# QCLogic_Rev_A_Sht8_MCU_Power.net
KiCad netlist of a schematic drawn in Altium Designer
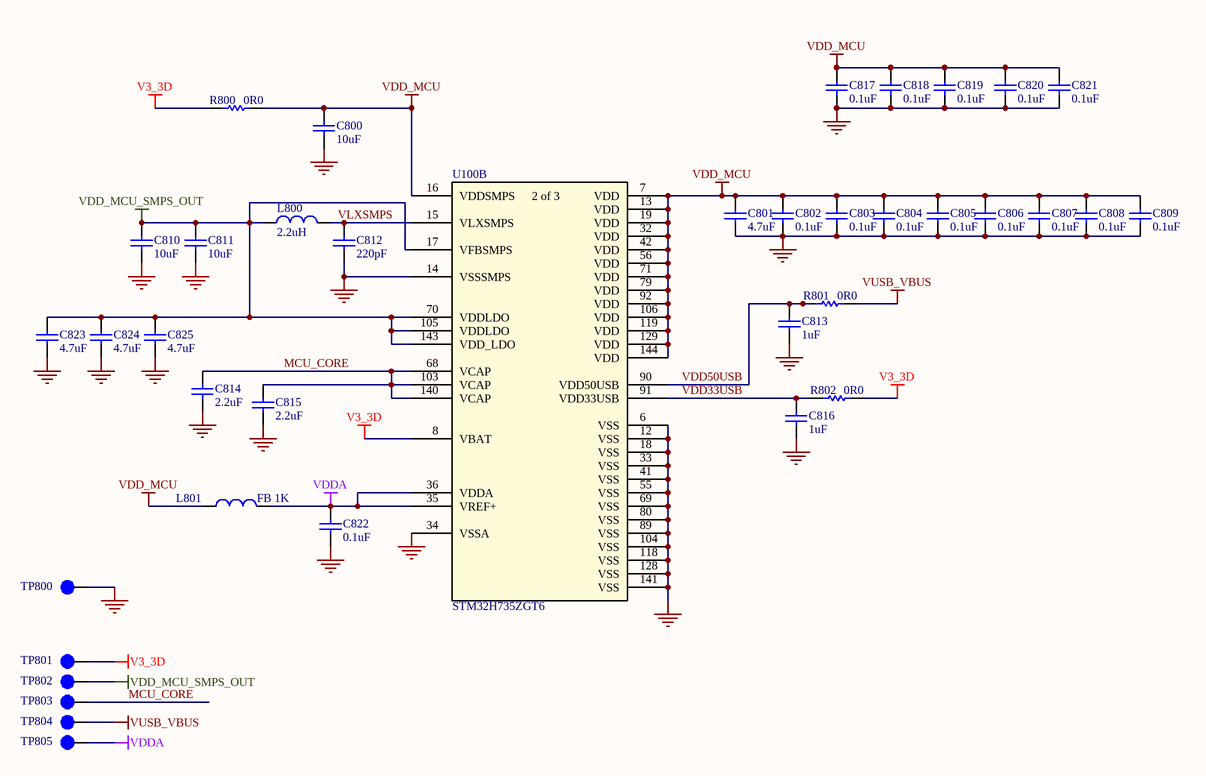
[diagram p0: QCLogic Rev A Sht8 MCU Power.SchDoc]

(export (version "E")
  (design (tool "Eeschema 10.0.6"))
  (components
    (comp (ref "C800")
      (value "10uF")
      (footprint "SMD CAP 0805")
      (description "CAP CER 10UF 25V X5R 0805")
      (fields (field (name "2. MANUFACTURER PART NUMBER") "TMK212BBJ106KG-T"))
      (libsource (lib "SBCLib") (part "CAP MLCC SMD"))
    )
    (comp (ref "C801")
      (value "4.7uF")
      (footprint "SMD CAP 0603")
      (description "CAP CER 4.7UF 16V X7S 0603")
      (fields (field (name "2. MANUFACTURER PART NUMBER") "GRM188C71C475KE21D"))
      (libsource (lib "SBCLib") (part "CAP MLCC SMD"))
    )
    (comp (ref "C802")
      (value "0.1uF")
      (footprint "SMD CAP 0402")
      (description "CAP CER 0.1UF 25V X7R 0402")
      (fields (field (name "2. MANUFACTURER PART NUMBER") "CC0402KRX7R8BB104"))
      (libsource (lib "SBCLib") (part "CAP MLCC SMD"))
    )
    (comp (ref "C803")
      (value "0.1uF")
      (footprint "SMD CAP 0402")
      (description "CAP CER 0.1UF 25V X7R 0402")
      (fields (field (name "2. MANUFACTURER PART NUMBER") "CC0402KRX7R8BB104"))
      (libsource (lib "SBCLib") (part "CAP MLCC SMD"))
    )
    (comp (ref "C804")
      (value "0.1uF")
      (footprint "SMD CAP 0402")
      (description "CAP CER 0.1UF 25V X7R 0402")
      (fields (field (name "2. MANUFACTURER PART NUMBER") "CC0402KRX7R8BB104"))
      (libsource (lib "SBCLib") (part "CAP MLCC SMD"))
    )
    (comp (ref "C805")
      (value "0.1uF")
      (footprint "SMD CAP 0402")
      (description "CAP CER 0.1UF 25V X7R 0402")
      (fields (field (name "2. MANUFACTURER PART NUMBER") "CC0402KRX7R8BB104"))
      (libsource (lib "SBCLib") (part "CAP MLCC SMD"))
    )
    (comp (ref "C806")
      (value "0.1uF")
      (footprint "SMD CAP 0402")
      (description "CAP CER 0.1UF 25V X7R 0402")
      (fields (field (name "2. MANUFACTURER PART NUMBER") "CC0402KRX7R8BB104"))
      (libsource (lib "SBCLib") (part "CAP MLCC SMD"))
    )
    (comp (ref "C807")
      (value "0.1uF")
      (footprint "SMD CAP 0402")
      (description "CAP CER 0.1UF 25V X7R 0402")
      (fields (field (name "2. MANUFACTURER PART NUMBER") "CC0402KRX7R8BB104"))
      (libsource (lib "SBCLib") (part "CAP MLCC SMD"))
    )
    (comp (ref "C808")
      (value "0.1uF")
      (footprint "SMD CAP 0402")
      (description "CAP CER 0.1UF 25V X7R 0402")
      (fields (field (name "2. MANUFACTURER PART NUMBER") "CC0402KRX7R8BB104"))
      (libsource (lib "SBCLib") (part "CAP MLCC SMD"))
    )
    (comp (ref "C809")
      (value "0.1uF")
      (footprint "SMD CAP 0402")
      (description "CAP CER 0.1UF 25V X7R 0402")
      (fields (field (name "2. MANUFACTURER PART NUMBER") "CC0402KRX7R8BB104"))
      (libsource (lib "SBCLib") (part "CAP MLCC SMD"))
    )
    (comp (ref "C810")
      (value "10uF")
      (footprint "SMD CAP 0805")
      (description "CAP CER 10UF 25V X5R 0805")
      (fields (field (name "2. MANUFACTURER PART NUMBER") "TMK212BBJ106KG-T"))
      (libsource (lib "SBCLib") (part "CAP MLCC SMD"))
    )
    (comp (ref "C811")
      (value "10uF")
      (footprint "SMD CAP 0805")
      (description "CAP CER 10UF 25V X5R 0805")
      (fields (field (name "2. MANUFACTURER PART NUMBER") "TMK212BBJ106KG-T"))
      (libsource (lib "SBCLib") (part "CAP MLCC SMD"))
    )
    (comp (ref "C812")
      (value "220pF")
      (footprint "SMD CAP 0402")
      (description "CAP CER 220PF 50V X7R 0402")
      (fields (field (name "2. MANUFACTURER PART NUMBER") "CC0402KRX7R9BB221"))
      (libsource (lib "SBCLib") (part "CAP MLCC SMD"))
    )
    (comp (ref "C813")
      (value "1uF")
      (footprint "SMD CAP 0402")
      (description "CAP CER 1UF 25V X5R 0402")
      (fields (field (name "2. MANUFACTURER PART NUMBER") "GRT155R61E105KE01D"))
      (libsource (lib "SBCLib") (part "CAP MLCC SMD"))
    )
    (comp (ref "C814")
      (value "2.2uF")
      (footprint "SMD CAP 0402")
      (description "CAP CER 2.2UF 16V X6S 0402")
      (fields (field (name "2. MANUFACTURER PART NUMBER") "GRM155C81C225ME15D"))
      (libsource (lib "SBCLib") (part "CAP MLCC SMD"))
    )
    (comp (ref "C815")
      (value "2.2uF")
      (footprint "SMD CAP 0402")
      (description "CAP CER 2.2UF 16V X6S 0402")
      (fields (field (name "2. MANUFACTURER PART NUMBER") "GRM155C81C225ME15D"))
      (libsource (lib "SBCLib") (part "CAP MLCC SMD"))
    )
    (comp (ref "C816")
      (value "1uF")
      (footprint "SMD CAP 0402")
      (description "CAP CER 1UF 25V X5R 0402")
      (fields (field (name "2. MANUFACTURER PART NUMBER") "GRT155R61E105KE01D"))
      (libsource (lib "SBCLib") (part "CAP MLCC SMD"))
    )
    (comp (ref "C817")
      (value "0.1uF")
      (footprint "SMD CAP 0402")
      (description "CAP CER 0.1UF 25V X7R 0402")
      (fields (field (name "2. MANUFACTURER PART NUMBER") "CC0402KRX7R8BB104"))
      (libsource (lib "SBCLib") (part "CAP MLCC SMD"))
    )
    (comp (ref "C818")
      (value "0.1uF")
      (footprint "SMD CAP 0402")
      (description "CAP CER 0.1UF 25V X7R 0402")
      (fields (field (name "2. MANUFACTURER PART NUMBER") "CC0402KRX7R8BB104"))
      (libsource (lib "SBCLib") (part "CAP MLCC SMD"))
    )
    (comp (ref "C819")
      (value "0.1uF")
      (footprint "SMD CAP 0402")
      (description "CAP CER 0.1UF 25V X7R 0402")
      (fields (field (name "2. MANUFACTURER PART NUMBER") "CC0402KRX7R8BB104"))
      (libsource (lib "SBCLib") (part "CAP MLCC SMD"))
    )
    (comp (ref "C820")
      (value "0.1uF")
      (footprint "SMD CAP 0402")
      (description "CAP CER 0.1UF 25V X7R 0402")
      (fields (field (name "2. MANUFACTURER PART NUMBER") "CC0402KRX7R8BB104"))
      (libsource (lib "SBCLib") (part "CAP MLCC SMD"))
    )
    (comp (ref "C821")
      (value "0.1uF")
      (footprint "SMD CAP 0402")
      (description "CAP CER 0.1UF 25V X7R 0402")
      (fields (field (name "2. MANUFACTURER PART NUMBER") "CC0402KRX7R8BB104"))
      (libsource (lib "SBCLib") (part "CAP MLCC SMD"))
    )
    (comp (ref "C822")
      (value "0.1uF")
      (footprint "SMD CAP 0402")
      (description "CAP CER 0.1UF 25V X7R 0402")
      (fields (field (name "2. MANUFACTURER PART NUMBER") "CC0402KRX7R8BB104"))
      (libsource (lib "SBCLib") (part "CAP MLCC SMD"))
    )
    (comp (ref "C823")
      (value "4.7uF")
      (footprint "SMD CAP 0603")
      (description "CAP CER 4.7UF 16V X7S 0603")
      (fields (field (name "2. MANUFACTURER PART NUMBER") "GRM188C71C475KE21D"))
      (libsource (lib "SBCLib") (part "CAP MLCC SMD"))
    )
    (comp (ref "C824")
      (value "4.7uF")
      (footprint "SMD CAP 0603")
      (description "CAP CER 4.7UF 16V X7S 0603")
      (fields (field (name "2. MANUFACTURER PART NUMBER") "GRM188C71C475KE21D"))
      (libsource (lib "SBCLib") (part "CAP MLCC SMD"))
    )
    (comp (ref "C825")
      (value "4.7uF")
      (footprint "SMD CAP 0603")
      (description "CAP CER 4.7UF 16V X7S 0603")
      (fields (field (name "2. MANUFACTURER PART NUMBER") "GRM188C71C475KE21D"))
      (libsource (lib "SBCLib") (part "CAP MLCC SMD"))
    )
    (comp (ref "L800")
      (value "2.2uH")
      (footprint "IND SMD 0806")
      (description "IND FIXED 2.2UH 1.2A 138 MOHM")
      (fields (field (name "2. MANUFACTURER PART NUMBER") "LQM2MPN2R2NG0L"))
      (libsource (lib "SBCLib") (part "INDUCTOR"))
    )
    (comp (ref "L801")
      (value "FB 1K")
      (footprint "SMD RES 0402")
      (description "FERRITE BEAD 1 KOHM 0402 1LN")
      (fields (field (name "2. MANUFACTURER PART NUMBER") "BLM15HD102SN1D"))
      (libsource (lib "SBCLib") (part "INDUCTOR"))
    )
    (comp (ref "R800")
      (value "0R0")
      (footprint "SMD RES 0402")
      (description "RES SMD 0 OHM JUMPER 1/16W 0402")
      (fields (field (name "2. MANUFACTURER PART NUMBER") "RC0402FR-070RL"))
      (libsource (lib "SBCLib") (part "RES SMD"))
    )
    (comp (ref "R801")
      (value "0R0")
      (footprint "SMD RES 0402")
      (description "RES SMD 0 OHM JUMPER 1/16W 0402")
      (fields (field (name "2. MANUFACTURER PART NUMBER") "RC0402FR-070RL"))
      (libsource (lib "SBCLib") (part "RES SMD"))
    )
    (comp (ref "R802")
      (value "0R0")
      (footprint "SMD RES 0402")
      (description "RES SMD 0 OHM JUMPER 1/16W 0402")
      (fields (field (name "2. MANUFACTURER PART NUMBER") "RC0402FR-070RL"))
      (libsource (lib "SBCLib") (part "RES SMD"))
    )
    (comp (ref "TP800")
      (value "TESTPOINT SMD")
      (footprint "TESTPOINT 1mm DIA")
      (description "TESTPOINT SMD PAD")
      (libsource (lib "SBCLib") (part "TESTPOINT PAD"))
    )
    (comp (ref "TP801")
      (value "TESTPOINT SMD")
      (footprint "TESTPOINT 0.5mm DIA")
      (description "TESTPOINT SMD PAD")
      (libsource (lib "SBCLib") (part "TESTPOINT PAD"))
    )
    (comp (ref "TP802")
      (value "TESTPOINT SMD")
      (footprint "TESTPOINT 0.5mm DIA")
      (description "TESTPOINT SMD PAD")
      (libsource (lib "SBCLib") (part "TESTPOINT PAD"))
    )
    (comp (ref "TP803")
      (value "TESTPOINT SMD")
      (footprint "TESTPOINT 0.5mm DIA")
      (description "TESTPOINT SMD PAD")
      (libsource (lib "SBCLib") (part "TESTPOINT PAD"))
    )
    (comp (ref "TP804")
      (value "TESTPOINT SMD")
      (footprint "TESTPOINT 0.5mm DIA")
      (description "TESTPOINT SMD PAD")
      (libsource (lib "SBCLib") (part "TESTPOINT PAD"))
    )
    (comp (ref "TP805")
      (value "TESTPOINT SMD")
      (footprint "TESTPOINT 0.5mm DIA")
      (description "TESTPOINT SMD PAD")
      (libsource (lib "SBCLib") (part "TESTPOINT PAD"))
    )
    (comp (ref "U100")
      (value "STM32H735ZGT6")
      (footprint "LQFP-144 20x20")
      (description "ARM® Cortex®-M7 STM32H7 Microcontroller IC 32-Bit 550MHz 1MB (1M x 8) FLASH 144 LQFP 20x20")
      (libsource (lib "SBCLib") (part "IC MCU STM32H735ZG Arm M7"))
    )
  )
  (nets
    (net (code "1") (name "/MCU_CORE") (class "Default")
      (node (ref "C814") (pin "2") (pinfunction "2_2") (pintype "passive"))
      (node (ref "C815") (pin "2") (pinfunction "2_2") (pintype "passive"))
      (node (ref "TP803") (pin "1") (pinfunction "1_1") (pintype "passive"))
      (node (ref "U100") (pin "103") (pinfunction "VCAP_103") (pintype "passive"))
      (node (ref "U100") (pin "140") (pinfunction "VCAP_140") (pintype "passive"))
      (node (ref "U100") (pin "68") (pinfunction "VCAP_68") (pintype "passive"))
    )
    (net (code "2") (name "/VDD33USB") (class "Default")
      (node (ref "C816") (pin "1") (pinfunction "1_1") (pintype "passive"))
      (node (ref "R802") (pin "1") (pinfunction "1_1") (pintype "passive"))
      (node (ref "U100") (pin "91") (pinfunction "VDD33USB_91") (pintype "passive"))
    )
    (net (code "3") (name "/VDD50USB") (class "Default")
      (node (ref "C813") (pin "1") (pinfunction "1_1") (pintype "passive"))
      (node (ref "R801") (pin "1") (pinfunction "1_1") (pintype "passive"))
      (node (ref "U100") (pin "90") (pinfunction "VDD50USB_90") (pintype "passive"))
    )
    (net (code "4") (name "/VLXSMPS") (class "Default")
      (node (ref "C812") (pin "2") (pinfunction "2_2") (pintype "passive"))
      (node (ref "L800") (pin "2") (pinfunction "2_2") (pintype "passive"))
      (node (ref "U100") (pin "15") (pinfunction "VLXSMPS_15") (pintype "passive"))
    )
    (net (code "5") (name "GND") (class "Default")
      (node (ref "C800") (pin "2") (pinfunction "2_2") (pintype "passive"))
      (node (ref "C801") (pin "2") (pinfunction "2_2") (pintype "passive"))
      (node (ref "C802") (pin "1") (pinfunction "1_1") (pintype "passive"))
      (node (ref "C803") (pin "1") (pinfunction "1_1") (pintype "passive"))
      (node (ref "C804") (pin "1") (pinfunction "1_1") (pintype "passive"))
      (node (ref "C805") (pin "1") (pinfunction "1_1") (pintype "passive"))
      (node (ref "C806") (pin "1") (pinfunction "1_1") (pintype "passive"))
      (node (ref "C807") (pin "1") (pinfunction "1_1") (pintype "passive"))
      (node (ref "C808") (pin "1") (pinfunction "1_1") (pintype "passive"))
      (node (ref "C809") (pin "1") (pinfunction "1_1") (pintype "passive"))
      (node (ref "C810") (pin "2") (pinfunction "2_2") (pintype "passive"))
      (node (ref "C811") (pin "2") (pinfunction "2_2") (pintype "passive"))
      (node (ref "C812") (pin "1") (pinfunction "1_1") (pintype "passive"))
      (node (ref "C813") (pin "2") (pinfunction "2_2") (pintype "passive"))
      (node (ref "C814") (pin "1") (pinfunction "1_1") (pintype "passive"))
      (node (ref "C815") (pin "1") (pinfunction "1_1") (pintype "passive"))
      (node (ref "C816") (pin "2") (pinfunction "2_2") (pintype "passive"))
      (node (ref "C817") (pin "1") (pinfunction "1_1") (pintype "passive"))
      (node (ref "C818") (pin "1") (pinfunction "1_1") (pintype "passive"))
      (node (ref "C819") (pin "1") (pinfunction "1_1") (pintype "passive"))
      (node (ref "C820") (pin "1") (pinfunction "1_1") (pintype "passive"))
      (node (ref "C821") (pin "1") (pinfunction "1_1") (pintype "passive"))
      (node (ref "C822") (pin "1") (pinfunction "1_1") (pintype "passive"))
      (node (ref "C823") (pin "2") (pinfunction "2_2") (pintype "passive"))
      (node (ref "C824") (pin "2") (pinfunction "2_2") (pintype "passive"))
      (node (ref "C825") (pin "2") (pinfunction "2_2") (pintype "passive"))
      (node (ref "TP800") (pin "1") (pinfunction "1_1") (pintype "passive"))
      (node (ref "U100") (pin "104") (pinfunction "VSS_104") (pintype "passive"))
      (node (ref "U100") (pin "118") (pinfunction "VSS_118") (pintype "passive"))
      (node (ref "U100") (pin "12") (pinfunction "VSS_12") (pintype "passive"))
      (node (ref "U100") (pin "128") (pinfunction "VSS_128") (pintype "passive"))
      (node (ref "U100") (pin "14") (pinfunction "VSSSMPS_14") (pintype "passive"))
      (node (ref "U100") (pin "141") (pinfunction "VSS_141") (pintype "passive"))
      (node (ref "U100") (pin "18") (pinfunction "VSS_18") (pintype "passive"))
      (node (ref "U100") (pin "33") (pinfunction "VSS_33") (pintype "passive"))
      (node (ref "U100") (pin "34") (pinfunction "VSSA_34") (pintype "passive"))
      (node (ref "U100") (pin "41") (pinfunction "VSS_41") (pintype "passive"))
      (node (ref "U100") (pin "55") (pinfunction "VSS_55") (pintype "passive"))
      (node (ref "U100") (pin "6") (pinfunction "VSS_6") (pintype "passive"))
      (node (ref "U100") (pin "69") (pinfunction "VSS_69") (pintype "passive"))
      (node (ref "U100") (pin "80") (pinfunction "VSS_80") (pintype "passive"))
      (node (ref "U100") (pin "89") (pinfunction "VSS_89") (pintype "passive"))
    )
    (net (code "6") (name "V3_3D") (class "Default")
      (node (ref "R800") (pin "1") (pinfunction "1_1") (pintype "passive"))
      (node (ref "R802") (pin "2") (pinfunction "2_2") (pintype "passive"))
      (node (ref "TP801") (pin "1") (pinfunction "1_1") (pintype "passive"))
      (node (ref "U100") (pin "8") (pinfunction "VBAT_8") (pintype "passive"))
    )
    (net (code "7") (name "VDDA") (class "Default")
      (node (ref "C822") (pin "2") (pinfunction "2_2") (pintype "passive"))
      (node (ref "L801") (pin "2") (pinfunction "2_2") (pintype "passive"))
      (node (ref "TP805") (pin "1") (pinfunction "1_1") (pintype "passive"))
      (node (ref "U100") (pin "35") (pinfunction "VREF+_35") (pintype "passive"))
      (node (ref "U100") (pin "36") (pinfunction "VDDA_36") (pintype "passive"))
    )
    (net (code "8") (name "VDD_MCU") (class "Default")
      (node (ref "C800") (pin "1") (pinfunction "1_1") (pintype "passive"))
      (node (ref "C801") (pin "1") (pinfunction "1_1") (pintype "passive"))
      (node (ref "C802") (pin "2") (pinfunction "2_2") (pintype "passive"))
      (node (ref "C803") (pin "2") (pinfunction "2_2") (pintype "passive"))
      (node (ref "C804") (pin "2") (pinfunction "2_2") (pintype "passive"))
      (node (ref "C805") (pin "2") (pinfunction "2_2") (pintype "passive"))
      (node (ref "C806") (pin "2") (pinfunction "2_2") (pintype "passive"))
      (node (ref "C807") (pin "2") (pinfunction "2_2") (pintype "passive"))
      (node (ref "C808") (pin "2") (pinfunction "2_2") (pintype "passive"))
      (node (ref "C809") (pin "2") (pinfunction "2_2") (pintype "passive"))
      (node (ref "C817") (pin "2") (pinfunction "2_2") (pintype "passive"))
      (node (ref "C818") (pin "2") (pinfunction "2_2") (pintype "passive"))
      (node (ref "C819") (pin "2") (pinfunction "2_2") (pintype "passive"))
      (node (ref "C820") (pin "2") (pinfunction "2_2") (pintype "passive"))
      (node (ref "C821") (pin "2") (pinfunction "2_2") (pintype "passive"))
      (node (ref "L801") (pin "1") (pinfunction "1_1") (pintype "passive"))
      (node (ref "R800") (pin "2") (pinfunction "2_2") (pintype "passive"))
      (node (ref "U100") (pin "106") (pinfunction "VDD_106") (pintype "passive"))
      (node (ref "U100") (pin "119") (pinfunction "VDD_119") (pintype "passive"))
      (node (ref "U100") (pin "129") (pinfunction "VDD_129") (pintype "passive"))
      (node (ref "U100") (pin "13") (pinfunction "VDD_13") (pintype "passive"))
      (node (ref "U100") (pin "144") (pinfunction "VDD_144") (pintype "passive"))
      (node (ref "U100") (pin "16") (pinfunction "VDDSMPS_16") (pintype "power_in"))
      (node (ref "U100") (pin "19") (pinfunction "VDD_19") (pintype "passive"))
      (node (ref "U100") (pin "32") (pinfunction "VDD_32") (pintype "passive"))
      (node (ref "U100") (pin "42") (pinfunction "VDD_42") (pintype "passive"))
      (node (ref "U100") (pin "56") (pinfunction "VDD_56") (pintype "passive"))
      (node (ref "U100") (pin "7") (pinfunction "VDD_7") (pintype "passive"))
      (node (ref "U100") (pin "71") (pinfunction "VDD_71") (pintype "passive"))
      (node (ref "U100") (pin "79") (pinfunction "VDD_79") (pintype "passive"))
      (node (ref "U100") (pin "92") (pinfunction "VDD_92") (pintype "passive"))
    )
    (net (code "9") (name "VDD_MCU_SMPS_OUT") (class "Default")
      (node (ref "C810") (pin "1") (pinfunction "1_1") (pintype "passive"))
      (node (ref "C811") (pin "1") (pinfunction "1_1") (pintype "passive"))
      (node (ref "C823") (pin "1") (pinfunction "1_1") (pintype "passive"))
      (node (ref "C824") (pin "1") (pinfunction "1_1") (pintype "passive"))
      (node (ref "C825") (pin "1") (pinfunction "1_1") (pintype "passive"))
      (node (ref "L800") (pin "1") (pinfunction "1_1") (pintype "passive"))
      (node (ref "TP802") (pin "1") (pinfunction "1_1") (pintype "passive"))
      (node (ref "U100") (pin "105") (pinfunction "VDDLDO_105") (pintype "passive"))
      (node (ref "U100") (pin "143") (pinfunction "VDD_LDO_143") (pintype "passive"))
      (node (ref "U100") (pin "17") (pinfunction "VFBSMPS_17") (pintype "passive"))
      (node (ref "U100") (pin "70") (pinfunction "VDDLDO_70") (pintype "passive"))
    )
    (net (code "10") (name "VUSB_VBUS") (class "Default")
      (node (ref "R801") (pin "2") (pinfunction "2_2") (pintype "passive"))
      (node (ref "TP804") (pin "1") (pinfunction "1_1") (pintype "passive"))
    )
  )
)
